# Uno.net
KiCad netlist of a schematic drawn in EAGLE
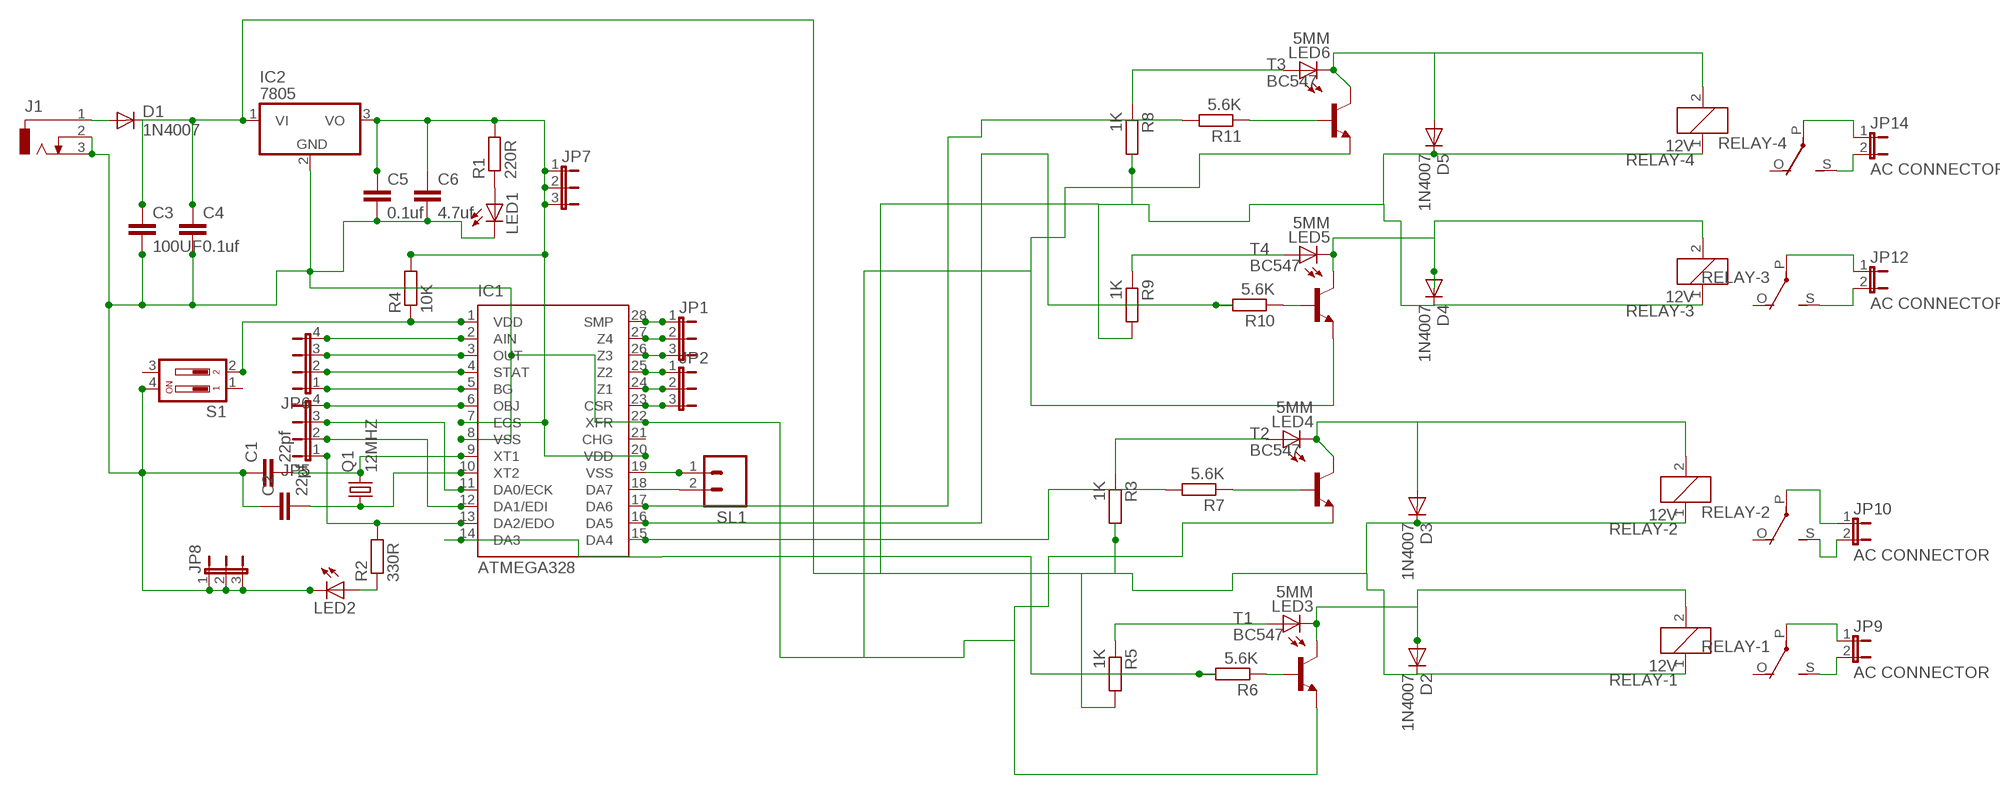
[diagram p0: schematic, sheet 1]

(export (version "E")
  (design (tool "Eeschema 10.0.6"))
  (components
    (comp (ref "C1")
      (value "22pf")
      (footprint "eagle-import:C2.5-2")
      (libsource (lib "eagle-import") (part "C2.5/2"))
    )
    (comp (ref "C2")
      (value "22pf")
      (footprint "eagle-import:C2.5-2")
      (libsource (lib "eagle-import") (part "C2.5/2"))
    )
    (comp (ref "C3")
      (value "100UF")
      (footprint "eagle-import:C2.5-2")
      (libsource (lib "eagle-import") (part "C2.5/2"))
    )
    (comp (ref "C4")
      (value "0.1uf")
      (footprint "eagle-import:C2.5-2")
      (libsource (lib "eagle-import") (part "C2.5/2"))
    )
    (comp (ref "C5")
      (value "0.1uf")
      (footprint "eagle-import:C2.5-2")
      (libsource (lib "eagle-import") (part "C2.5/2"))
    )
    (comp (ref "C6")
      (value "4.7uf")
      (footprint "eagle-import:C2.5-2")
      (libsource (lib "eagle-import") (part "C2.5/2"))
    )
    (comp (ref "D1")
      (value "1N4007")
      (footprint "eagle-import:DO41-10")
      (libsource (lib "eagle-import") (part "1N4004"))
    )
    (comp (ref "D2")
      (value "1N4007")
      (footprint "eagle-import:DO41-10")
      (libsource (lib "eagle-import") (part "1N4004"))
    )
    (comp (ref "D3")
      (value "1N4007")
      (footprint "eagle-import:DO41-10")
      (libsource (lib "eagle-import") (part "1N4004"))
    )
    (comp (ref "D4")
      (value "1N4007")
      (footprint "eagle-import:DO41-10")
      (libsource (lib "eagle-import") (part "1N4004"))
    )
    (comp (ref "D5")
      (value "1N4007")
      (footprint "eagle-import:DO41-10")
      (libsource (lib "eagle-import") (part "1N4004"))
    )
    (comp (ref "IC1")
      (value "ATMEGA328")
      (footprint "eagle-import:DIL28-3")
      (libsource (lib "eagle-import") (part "QT9701BD"))
    )
    (comp (ref "IC2")
      (value "7805")
      (footprint "eagle-import:TO220V")
      (libsource (lib "eagle-import") (part "78TV6"))
    )
    (comp (ref "J1")
      (value "DCJ0303")
      (footprint "eagle-import:DCJ0303")
      (libsource (lib "eagle-import") (part "DCJ0303"))
    )
    (comp (ref "JP1")
      (value "JP2E")
      (footprint "eagle-import:JP2")
      (libsource (lib "eagle-import") (part "JP2E"))
    )
    (comp (ref "JP2")
      (value "JP2E")
      (footprint "eagle-import:JP2")
      (libsource (lib "eagle-import") (part "JP2E"))
    )
    (comp (ref "JP5")
      (value "JP4E")
      (footprint "eagle-import:JP4")
      (libsource (lib "eagle-import") (part "JP4E"))
    )
    (comp (ref "JP6")
      (value "JP4E")
      (footprint "eagle-import:JP4")
      (libsource (lib "eagle-import") (part "JP4E"))
    )
    (comp (ref "JP7")
      (value "JP2E")
      (footprint "eagle-import:JP2")
      (libsource (lib "eagle-import") (part "JP2E"))
    )
    (comp (ref "JP8")
      (value "JP2E")
      (footprint "eagle-import:JP2")
      (libsource (lib "eagle-import") (part "JP2E"))
    )
    (comp (ref "JP9")
      (value "AC CONNECTOR")
      (footprint "eagle-import:JP1")
      (libsource (lib "eagle-import") (part "JP1E"))
    )
    (comp (ref "JP10")
      (value "AC CONNECTOR")
      (footprint "eagle-import:JP1")
      (libsource (lib "eagle-import") (part "JP1E"))
    )
    (comp (ref "JP12")
      (value "AC CONNECTOR")
      (footprint "eagle-import:JP1")
      (libsource (lib "eagle-import") (part "JP1E"))
    )
    (comp (ref "JP14")
      (value "AC CONNECTOR")
      (footprint "eagle-import:JP1")
      (libsource (lib "eagle-import") (part "JP1E"))
    )
    (comp (ref "LED1")
      (value "LED3MM")
      (footprint "eagle-import:LED3MM")
      (libsource (lib "eagle-import") (part "LED3MM"))
    )
    (comp (ref "LED2")
      (value "LED3MM")
      (footprint "eagle-import:LED3MM")
      (libsource (lib "eagle-import") (part "LED3MM"))
    )
    (comp (ref "LED3")
      (value "5MM")
      (footprint "eagle-import:LED5MM")
      (libsource (lib "eagle-import") (part "LED5MM"))
    )
    (comp (ref "LED4")
      (value "5MM")
      (footprint "eagle-import:LED5MM")
      (libsource (lib "eagle-import") (part "LED5MM"))
    )
    (comp (ref "LED5")
      (value "5MM")
      (footprint "eagle-import:LED5MM")
      (libsource (lib "eagle-import") (part "LED5MM"))
    )
    (comp (ref "LED6")
      (value "5MM")
      (footprint "eagle-import:LED5MM")
      (libsource (lib "eagle-import") (part "LED5MM"))
    )
    (comp (ref "Q1")
      (value "12MHZ")
      (footprint "eagle-import:HC49_S")
      (libsource (lib "eagle-import") (part "CRYSTALHC49S"))
    )
    (comp (ref "R1")
      (value "220R")
      (footprint "eagle-import:0207_10")
      (libsource (lib "eagle-import") (part "R-EU_0207/10"))
    )
    (comp (ref "R2")
      (value "330R")
      (footprint "eagle-import:0207_10")
      (libsource (lib "eagle-import") (part "R-EU_0207/10"))
    )
    (comp (ref "R3")
      (value "1K")
      (footprint "eagle-import:0204_7")
      (libsource (lib "eagle-import") (part "R-EU_0204/7"))
    )
    (comp (ref "R4")
      (value "10K")
      (footprint "eagle-import:0207_10")
      (libsource (lib "eagle-import") (part "R-EU_0207/10"))
    )
    (comp (ref "R5")
      (value "1K")
      (footprint "eagle-import:0204_7")
      (libsource (lib "eagle-import") (part "R-EU_0204/7"))
    )
    (comp (ref "R6")
      (value "5.6K")
      (footprint "eagle-import:0204_7")
      (libsource (lib "eagle-import") (part "R-EU_0204/7"))
    )
    (comp (ref "R7")
      (value "5.6K")
      (footprint "eagle-import:0204_7")
      (libsource (lib "eagle-import") (part "R-EU_0204/7"))
    )
    (comp (ref "R8")
      (value "1K")
      (footprint "eagle-import:0204_7")
      (libsource (lib "eagle-import") (part "R-EU_0204/7"))
    )
    (comp (ref "R9")
      (value "1K")
      (footprint "eagle-import:0204_7")
      (libsource (lib "eagle-import") (part "R-EU_0204/7"))
    )
    (comp (ref "R10")
      (value "5.6K")
      (footprint "eagle-import:0204_7")
      (libsource (lib "eagle-import") (part "R-EU_0204/7"))
    )
    (comp (ref "R11")
      (value "5.6K")
      (footprint "eagle-import:0204_7")
      (libsource (lib "eagle-import") (part "R-EU_0204/7"))
    )
    (comp (ref "RELAY-1")
      (value "12V")
      (footprint "eagle-import:G5LE")
      (libsource (lib "eagle-import") (part "G5L"))
    )
    (comp (ref "RELAY-2")
      (value "12V")
      (footprint "eagle-import:G5LE")
      (libsource (lib "eagle-import") (part "G5L"))
    )
    (comp (ref "RELAY-3")
      (value "12V")
      (footprint "eagle-import:G5LE")
      (libsource (lib "eagle-import") (part "G5L"))
    )
    (comp (ref "RELAY-4")
      (value "12V")
      (footprint "eagle-import:G5LE")
      (libsource (lib "eagle-import") (part "G5L"))
    )
    (comp (ref "S1")
      (value "DP02")
      (footprint "eagle-import:DP-02")
      (fields (field (name "MPN") "MCDP02"))
      (libsource (lib "eagle-import") (part "DP02"))
    )
    (comp (ref "SL1")
      (value "M02")
      (footprint "eagle-import:02P")
      (libsource (lib "eagle-import") (part "M02"))
    )
    (comp (ref "T1")
      (value "BC547")
      (footprint "eagle-import:TO92")
      (libsource (lib "eagle-import") (part "BC547"))
    )
    (comp (ref "T2")
      (value "BC547")
      (footprint "eagle-import:TO92")
      (libsource (lib "eagle-import") (part "BC547"))
    )
    (comp (ref "T3")
      (value "BC547")
      (footprint "eagle-import:TO92")
      (libsource (lib "eagle-import") (part "BC547"))
    )
    (comp (ref "T4")
      (value "BC547")
      (footprint "eagle-import:TO92")
      (libsource (lib "eagle-import") (part "BC547"))
    )
  )
  (nets
    (net (code "1") (name "Net-(D1-PadA)") (class "Default")
      (node (ref "D1") (pin "A") (pinfunction "A_A") (pintype "passive"))
      (node (ref "J1") (pin "1") (pinfunction "1_1") (pintype "passive"))
    )
    (net (code "2") (name "Net-(IC1-AIN)") (class "Default")
      (node (ref "IC1") (pin "2") (pinfunction "AIN_2") (pintype "input"))
      (node (ref "JP6") (pin "4") (pinfunction "4_4") (pintype "passive"))
    )
    (net (code "3") (name "Net-(IC1-BG)") (class "Default")
      (node (ref "IC1") (pin "5") (pinfunction "BG_5") (pintype "input"))
      (node (ref "JP6") (pin "1") (pinfunction "1_1") (pintype "passive"))
    )
    (net (code "4") (name "Net-(IC1-CSR)") (class "Default")
      (node (ref "IC1") (pin "23") (pinfunction "CSR_23") (pintype "output"))
      (node (ref "JP2") (pin "3") (pinfunction "3_3") (pintype "passive"))
    )
    (net (code "5") (name "Net-(IC1-DA0{slash}ECK)") (class "Default")
      (node (ref "IC1") (pin "11") (pinfunction "DA0/ECK_11") (pintype "output"))
      (node (ref "JP5") (pin "3") (pinfunction "3_3") (pintype "passive"))
    )
    (net (code "6") (name "Net-(IC1-DA1{slash}EDI)") (class "Default")
      (node (ref "IC1") (pin "12") (pinfunction "DA1/EDI_12") (pintype "output"))
      (node (ref "JP5") (pin "2") (pinfunction "2_2") (pintype "passive"))
    )
    (net (code "7") (name "Net-(IC1-DA2{slash}EDO)") (class "Default")
      (node (ref "IC1") (pin "13") (pinfunction "DA2/EDO_13") (pintype "output"))
      (node (ref "JP5") (pin "1") (pinfunction "1_1") (pintype "passive"))
      (node (ref "R2") (pin "2") (pinfunction "2_2") (pintype "passive"))
    )
    (net (code "8") (name "Net-(IC1-DA3)") (class "Default")
      (node (ref "IC1") (pin "14") (pinfunction "DA3_14") (pintype "output"))
      (node (ref "R6") (pin "2") (pinfunction "2_2") (pintype "passive"))
    )
    (net (code "9") (name "Net-(IC1-DA4)") (class "Default")
      (node (ref "IC1") (pin "15") (pinfunction "DA4_15") (pintype "output"))
      (node (ref "R7") (pin "2") (pinfunction "2_2") (pintype "passive"))
    )
    (net (code "10") (name "Net-(IC1-DA5)") (class "Default")
      (node (ref "IC1") (pin "16") (pinfunction "DA5_16") (pintype "output"))
      (node (ref "R10") (pin "2") (pinfunction "2_2") (pintype "passive"))
    )
    (net (code "11") (name "Net-(IC1-DA6)") (class "Default")
      (node (ref "IC1") (pin "17") (pinfunction "DA6_17") (pintype "output"))
      (node (ref "R11") (pin "2") (pinfunction "2_2") (pintype "passive"))
    )
    (net (code "12") (name "Net-(IC1-DA7)") (class "Default")
      (node (ref "IC1") (pin "18") (pinfunction "DA7_18") (pintype "output"))
      (node (ref "SL1") (pin "2") (pinfunction "2_2") (pintype "passive"))
    )
    (net (code "13") (name "Net-(IC1-ECS)") (class "Default")
      (node (ref "C5") (pin "1") (pinfunction "1_1") (pintype "passive"))
      (node (ref "C6") (pin "1") (pinfunction "1_1") (pintype "passive"))
      (node (ref "IC1") (pin "20") (pinfunction "VDD_20") (pintype "input"))
      (node (ref "IC1") (pin "7") (pinfunction "ECS_7") (pintype "output"))
      (node (ref "IC2") (pin "3") (pinfunction "VO_3") (pintype "passive"))
      (node (ref "JP7") (pin "1") (pinfunction "1_1") (pintype "passive"))
      (node (ref "JP7") (pin "2") (pinfunction "2_2") (pintype "passive"))
      (node (ref "JP7") (pin "3") (pinfunction "3_3") (pintype "passive"))
      (node (ref "R1") (pin "2") (pinfunction "2_2") (pintype "passive"))
      (node (ref "R4") (pin "2") (pinfunction "2_2") (pintype "passive"))
    )
    (net (code "14") (name "Net-(IC1-OBJ)") (class "Default")
      (node (ref "IC1") (pin "6") (pinfunction "OBJ_6") (pintype "input"))
      (node (ref "JP5") (pin "4") (pinfunction "4_4") (pintype "passive"))
    )
    (net (code "15") (name "Net-(IC1-OUT)") (class "Default")
      (node (ref "IC1") (pin "3") (pinfunction "OUT_3") (pintype "output"))
      (node (ref "JP6") (pin "3") (pinfunction "3_3") (pintype "passive"))
    )
    (net (code "16") (name "Net-(IC1-SMP)") (class "Default")
      (node (ref "IC1") (pin "28") (pinfunction "SMP_28") (pintype "output"))
      (node (ref "JP1") (pin "1") (pinfunction "1_1") (pintype "passive"))
    )
    (net (code "17") (name "Net-(IC1-STAT)") (class "Default")
      (node (ref "IC1") (pin "4") (pinfunction "STAT_4") (pintype "output"))
      (node (ref "JP6") (pin "2") (pinfunction "2_2") (pintype "passive"))
    )
    (net (code "18") (name "Net-(IC1-VDD-Pad1)") (class "Default")
      (node (ref "IC1") (pin "1") (pinfunction "VDD_1") (pintype "input"))
      (node (ref "R4") (pin "1") (pinfunction "1_1") (pintype "passive"))
      (node (ref "S1") (pin "2") (pinfunction "2_2") (pintype "passive"))
    )
    (net (code "19") (name "Net-(IC1-VSS-Pad19)") (class "Default")
      (node (ref "IC1") (pin "19") (pinfunction "VSS_19") (pintype "input"))
      (node (ref "SL1") (pin "1") (pinfunction "1_1") (pintype "passive"))
    )
    (net (code "20") (name "Net-(IC1-XFR)") (class "Default")
      (node (ref "C1") (pin "1") (pinfunction "1_1") (pintype "passive"))
      (node (ref "C2") (pin "1") (pinfunction "1_1") (pintype "passive"))
      (node (ref "C3") (pin "2") (pinfunction "2_2") (pintype "passive"))
      (node (ref "C4") (pin "2") (pinfunction "2_2") (pintype "passive"))
      (node (ref "C5") (pin "2") (pinfunction "2_2") (pintype "passive"))
      (node (ref "C6") (pin "2") (pinfunction "2_2") (pintype "passive"))
      (node (ref "IC1") (pin "22") (pinfunction "XFR_22") (pintype "output"))
      (node (ref "IC1") (pin "8") (pinfunction "VSS_8") (pintype "input"))
      (node (ref "IC2") (pin "2") (pinfunction "GND_2") (pintype "passive"))
      (node (ref "J1") (pin "2") (pinfunction "2_2") (pintype "passive"))
      (node (ref "J1") (pin "3") (pinfunction "3_3") (pintype "passive"))
      (node (ref "JP8") (pin "1") (pinfunction "1_1") (pintype "passive"))
      (node (ref "JP8") (pin "2") (pinfunction "2_2") (pintype "passive"))
      (node (ref "JP8") (pin "3") (pinfunction "3_3") (pintype "passive"))
      (node (ref "LED1") (pin "K") (pinfunction "C_K") (pintype "passive"))
      (node (ref "LED2") (pin "K") (pinfunction "C_K") (pintype "passive"))
      (node (ref "S1") (pin "4") (pinfunction "4_4") (pintype "passive"))
      (node (ref "T1") (pin "1") (pinfunction "E_1") (pintype "passive"))
      (node (ref "T2") (pin "1") (pinfunction "E_1") (pintype "passive"))
      (node (ref "T3") (pin "1") (pinfunction "E_1") (pintype "passive"))
      (node (ref "T4") (pin "1") (pinfunction "E_1") (pintype "passive"))
    )
    (net (code "21") (name "Net-(IC1-XT1)") (class "Default")
      (node (ref "C1") (pin "2") (pinfunction "2_2") (pintype "passive"))
      (node (ref "IC1") (pin "9") (pinfunction "XT1_9") (pintype "input"))
      (node (ref "Q1") (pin "2") (pinfunction "2_2") (pintype "passive"))
    )
    (net (code "22") (name "Net-(IC1-XT2)") (class "Default")
      (node (ref "C2") (pin "2") (pinfunction "2_2") (pintype "passive"))
      (node (ref "IC1") (pin "10") (pinfunction "XT2_10") (pintype "output"))
      (node (ref "Q1") (pin "1") (pinfunction "1_1") (pintype "passive"))
    )
    (net (code "23") (name "Net-(IC1-Z1)") (class "Default")
      (node (ref "IC1") (pin "24") (pinfunction "Z1_24") (pintype "output"))
      (node (ref "JP2") (pin "2") (pinfunction "2_2") (pintype "passive"))
    )
    (net (code "24") (name "Net-(IC1-Z2)") (class "Default")
      (node (ref "IC1") (pin "25") (pinfunction "Z2_25") (pintype "output"))
      (node (ref "JP2") (pin "1") (pinfunction "1_1") (pintype "passive"))
    )
    (net (code "25") (name "Net-(IC1-Z3)") (class "Default")
      (node (ref "IC1") (pin "26") (pinfunction "Z3_26") (pintype "output"))
      (node (ref "JP1") (pin "3") (pinfunction "3_3") (pintype "passive"))
    )
    (net (code "26") (name "Net-(IC1-Z4)") (class "Default")
      (node (ref "IC1") (pin "27") (pinfunction "Z4_27") (pintype "output"))
      (node (ref "JP1") (pin "2") (pinfunction "2_2") (pintype "passive"))
    )
    (net (code "27") (name "Net-(IC2-VI)") (class "Default")
      (node (ref "C3") (pin "1") (pinfunction "1_1") (pintype "passive"))
      (node (ref "C4") (pin "1") (pinfunction "1_1") (pintype "passive"))
      (node (ref "D1") (pin "C") (pinfunction "C_C") (pintype "passive"))
      (node (ref "D2") (pin "C") (pinfunction "C_C") (pintype "passive"))
      (node (ref "D3") (pin "C") (pinfunction "C_C") (pintype "passive"))
      (node (ref "D4") (pin "C") (pinfunction "C_C") (pintype "passive"))
      (node (ref "D5") (pin "C") (pinfunction "C_C") (pintype "passive"))
      (node (ref "IC2") (pin "1") (pinfunction "VI_1") (pintype "input"))
      (node (ref "R3") (pin "2") (pinfunction "2_2") (pintype "passive"))
      (node (ref "R5") (pin "2") (pinfunction "2_2") (pintype "passive"))
      (node (ref "R8") (pin "2") (pinfunction "2_2") (pintype "passive"))
      (node (ref "R9") (pin "2") (pinfunction "2_2") (pintype "passive"))
      (node (ref "RELAY-1") (pin "1") (pinfunction "1_1") (pintype "passive"))
      (node (ref "RELAY-2") (pin "1") (pinfunction "1_1") (pintype "passive"))
      (node (ref "RELAY-3") (pin "1") (pinfunction "1_1") (pintype "passive"))
      (node (ref "RELAY-4") (pin "1") (pinfunction "1_1") (pintype "passive"))
    )
    (net (code "28") (name "Net-(JP9-Pad1)") (class "Default")
      (node (ref "JP9") (pin "1") (pinfunction "1_1") (pintype "passive"))
      (node (ref "RELAY-1") (pin "P") (pinfunction "P_P") (pintype "passive"))
    )
    (net (code "29") (name "Net-(JP9-Pad2)") (class "Default")
      (node (ref "JP9") (pin "2") (pinfunction "2_2") (pintype "passive"))
      (node (ref "RELAY-1") (pin "S") (pinfunction "S_S") (pintype "passive"))
    )
    (net (code "30") (name "Net-(JP10-Pad1)") (class "Default")
      (node (ref "JP10") (pin "1") (pinfunction "1_1") (pintype "passive"))
      (node (ref "RELAY-2") (pin "P") (pinfunction "P_P") (pintype "passive"))
    )
    (net (code "31") (name "Net-(JP10-Pad2)") (class "Default")
      (node (ref "JP10") (pin "2") (pinfunction "2_2") (pintype "passive"))
      (node (ref "RELAY-2") (pin "S") (pinfunction "S_S") (pintype "passive"))
    )
    (net (code "32") (name "Net-(JP12-Pad1)") (class "Default")
      (node (ref "JP12") (pin "1") (pinfunction "1_1") (pintype "passive"))
      (node (ref "RELAY-3") (pin "P") (pinfunction "P_P") (pintype "passive"))
    )
    (net (code "33") (name "Net-(JP12-Pad2)") (class "Default")
      (node (ref "JP12") (pin "2") (pinfunction "2_2") (pintype "passive"))
      (node (ref "RELAY-3") (pin "S") (pinfunction "S_S") (pintype "passive"))
    )
    (net (code "34") (name "Net-(JP14-Pad1)") (class "Default")
      (node (ref "JP14") (pin "1") (pinfunction "1_1") (pintype "passive"))
      (node (ref "RELAY-4") (pin "P") (pinfunction "P_P") (pintype "passive"))
    )
    (net (code "35") (name "Net-(JP14-Pad2)") (class "Default")
      (node (ref "JP14") (pin "2") (pinfunction "2_2") (pintype "passive"))
      (node (ref "RELAY-4") (pin "S") (pinfunction "S_S") (pintype "passive"))
    )
    (net (code "36") (name "Net-(LED1-PadA)") (class "Default")
      (node (ref "LED1") (pin "A") (pinfunction "A_A") (pintype "passive"))
      (node (ref "R1") (pin "1") (pinfunction "1_1") (pintype "passive"))
    )
    (net (code "37") (name "Net-(LED2-PadA)") (class "Default")
      (node (ref "LED2") (pin "A") (pinfunction "A_A") (pintype "passive"))
      (node (ref "R2") (pin "1") (pinfunction "1_1") (pintype "passive"))
    )
    (net (code "38") (name "Net-(LED3-C)") (class "Default")
      (node (ref "D2") (pin "A") (pinfunction "A_A") (pintype "passive"))
      (node (ref "LED3") (pin "K") (pinfunction "C_K") (pintype "passive"))
      (node (ref "RELAY-1") (pin "2") (pinfunction "2_2") (pintype "passive"))
      (node (ref "T1") (pin "3") (pinfunction "C_3") (pintype "passive"))
    )
    (net (code "39") (name "Net-(LED3-PadA)") (class "Default")
      (node (ref "LED3") (pin "A") (pinfunction "A_A") (pintype "passive"))
      (node (ref "R5") (pin "1") (pinfunction "1_1") (pintype "passive"))
    )
    (net (code "40") (name "Net-(LED4-C)") (class "Default")
      (node (ref "D3") (pin "A") (pinfunction "A_A") (pintype "passive"))
      (node (ref "LED4") (pin "K") (pinfunction "C_K") (pintype "passive"))
      (node (ref "RELAY-2") (pin "2") (pinfunction "2_2") (pintype "passive"))
      (node (ref "T2") (pin "3") (pinfunction "C_3") (pintype "passive"))
    )
    (net (code "41") (name "Net-(LED4-PadA)") (class "Default")
      (node (ref "LED4") (pin "A") (pinfunction "A_A") (pintype "passive"))
      (node (ref "R3") (pin "1") (pinfunction "1_1") (pintype "passive"))
    )
    (net (code "42") (name "Net-(LED5-C)") (class "Default")
      (node (ref "D4") (pin "A") (pinfunction "A_A") (pintype "passive"))
      (node (ref "LED5") (pin "K") (pinfunction "C_K") (pintype "passive"))
      (node (ref "RELAY-3") (pin "2") (pinfunction "2_2") (pintype "passive"))
      (node (ref "T4") (pin "3") (pinfunction "C_3") (pintype "passive"))
    )
    (net (code "43") (name "Net-(LED5-PadA)") (class "Default")
      (node (ref "LED5") (pin "A") (pinfunction "A_A") (pintype "passive"))
      (node (ref "R9") (pin "1") (pinfunction "1_1") (pintype "passive"))
    )
    (net (code "44") (name "Net-(LED6-C)") (class "Default")
      (node (ref "D5") (pin "A") (pinfunction "A_A") (pintype "passive"))
      (node (ref "LED6") (pin "K") (pinfunction "C_K") (pintype "passive"))
      (node (ref "RELAY-4") (pin "2") (pinfunction "2_2") (pintype "passive"))
      (node (ref "T3") (pin "3") (pinfunction "C_3") (pintype "passive"))
    )
    (net (code "45") (name "Net-(LED6-PadA)") (class "Default")
      (node (ref "LED6") (pin "A") (pinfunction "A_A") (pintype "passive"))
      (node (ref "R8") (pin "1") (pinfunction "1_1") (pintype "passive"))
    )
    (net (code "46") (name "Net-(T1-B)") (class "Default")
      (node (ref "R6") (pin "1") (pinfunction "1_1") (pintype "passive"))
      (node (ref "T1") (pin "2") (pinfunction "B_2") (pintype "passive"))
    )
    (net (code "47") (name "Net-(T2-B)") (class "Default")
      (node (ref "R7") (pin "1") (pinfunction "1_1") (pintype "passive"))
      (node (ref "T2") (pin "2") (pinfunction "B_2") (pintype "passive"))
    )
    (net (code "48") (name "Net-(T3-B)") (class "Default")
      (node (ref "R11") (pin "1") (pinfunction "1_1") (pintype "passive"))
      (node (ref "T3") (pin "2") (pinfunction "B_2") (pintype "passive"))
    )
    (net (code "49") (name "Net-(T4-B)") (class "Default")
      (node (ref "R10") (pin "1") (pinfunction "1_1") (pintype "passive"))
      (node (ref "T4") (pin "2") (pinfunction "B_2") (pintype "passive"))
    )
    (net (code "50") (name "unconnected-(IC1-CHG-Pad21)") (class "Default")
      (node (ref "IC1") (pin "21") (pinfunction "CHG_21") (pintype "output"))
    )
    (net (code "51") (name "unconnected-(RELAY-1-PadO)") (class "Default")
      (node (ref "RELAY-1") (pin "O") (pinfunction "O_O") (pintype "passive"))
    )
    (net (code "52") (name "unconnected-(RELAY-2-PadO)") (class "Default")
      (node (ref "RELAY-2") (pin "O") (pinfunction "O_O") (pintype "passive"))
    )
    (net (code "53") (name "unconnected-(RELAY-3-PadO)") (class "Default")
      (node (ref "RELAY-3") (pin "O") (pinfunction "O_O") (pintype "passive"))
    )
    (net (code "54") (name "unconnected-(RELAY-4-PadO)") (class "Default")
      (node (ref "RELAY-4") (pin "O") (pinfunction "O_O") (pintype "passive"))
    )
    (net (code "55") (name "unconnected-(S1-Pad1)") (class "Default")
      (node (ref "S1") (pin "1") (pinfunction "1_1") (pintype "passive"))
    )
    (net (code "56") (name "unconnected-(S1-Pad3)") (class "Default")
      (node (ref "S1") (pin "3") (pinfunction "3_3") (pintype "passive"))
    )
  )
)
